# datalogger-v10.net
KiCad netlist of a schematic drawn in EAGLE
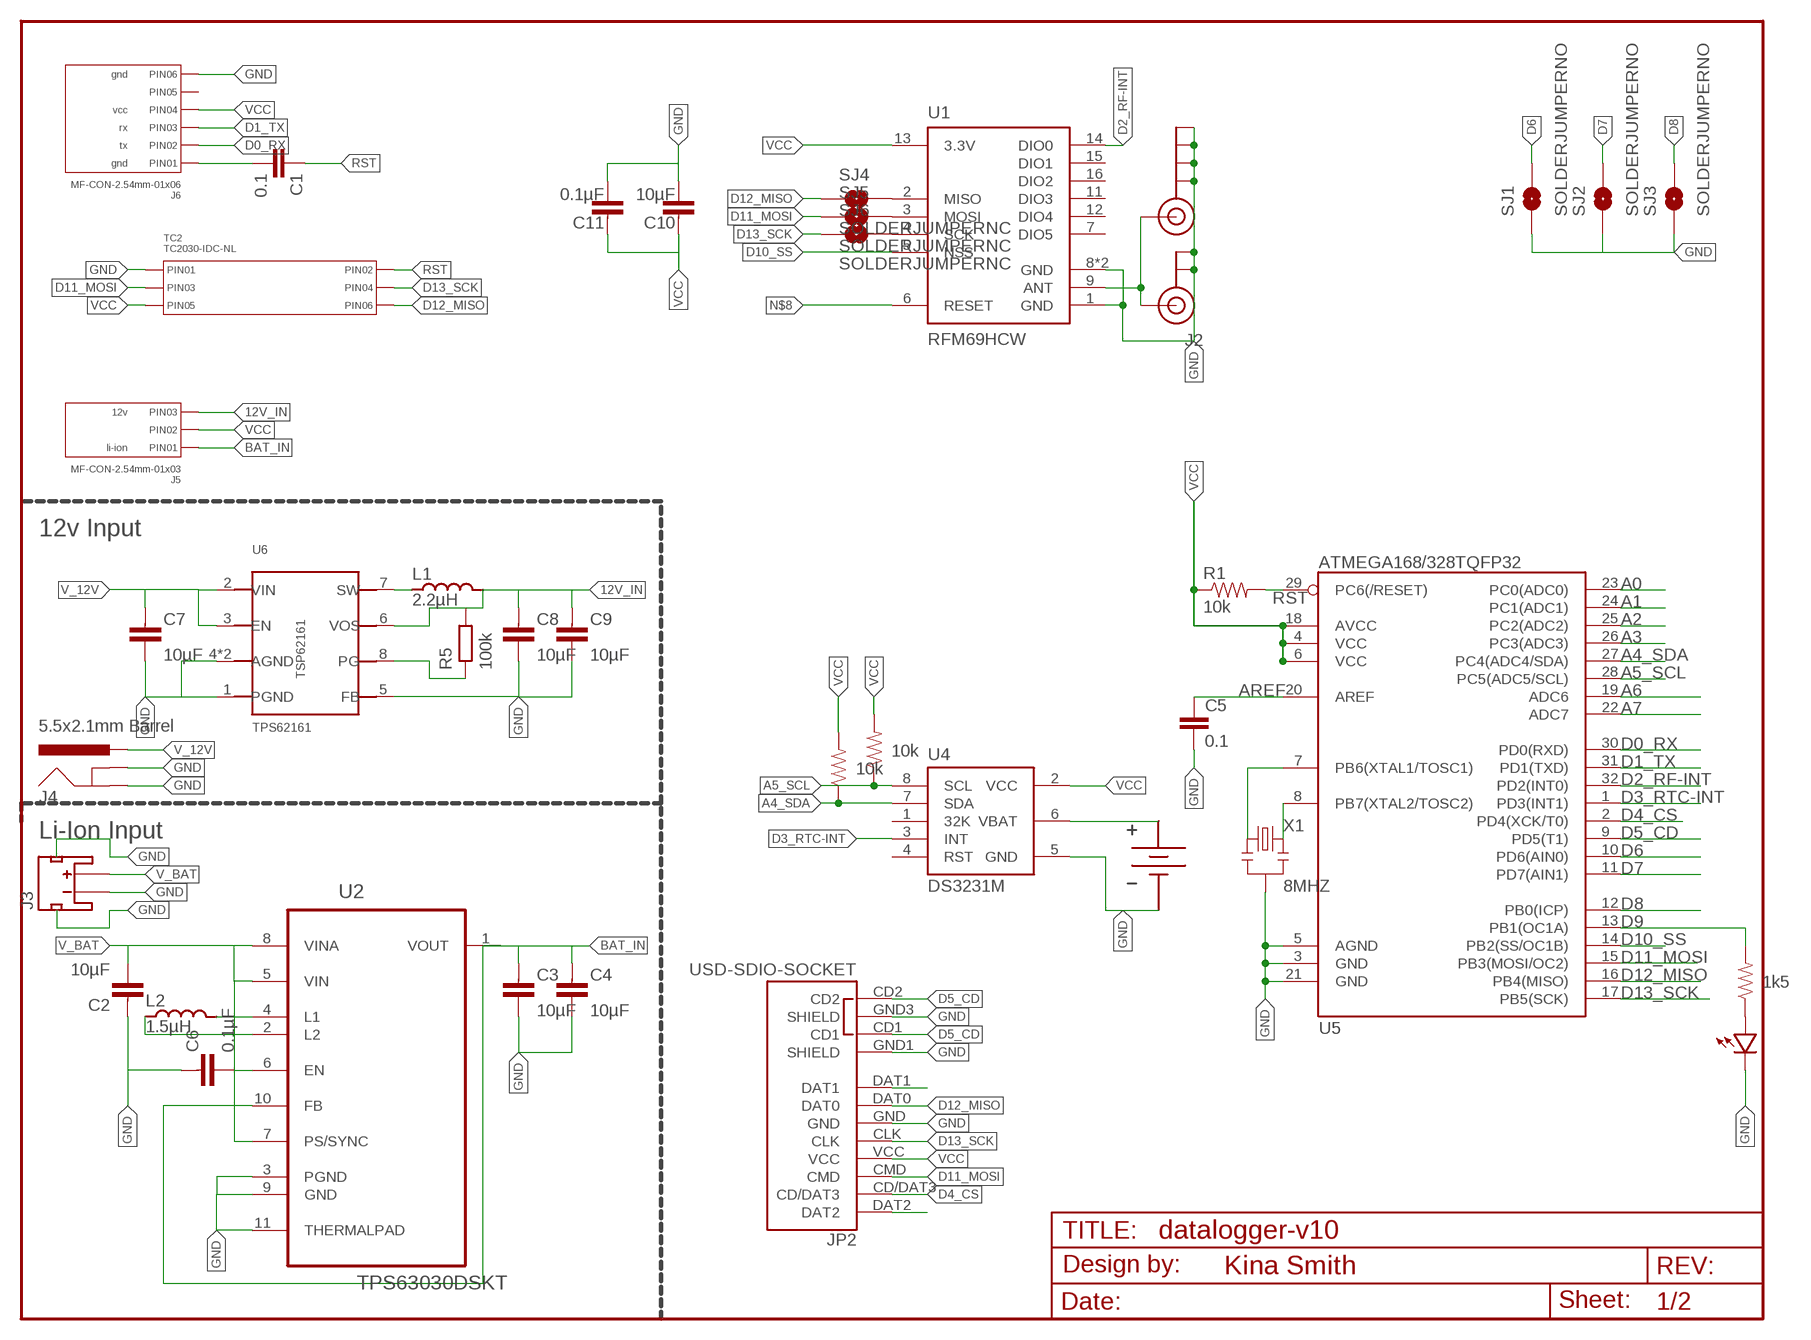
[diagram p0: schematic, sheet 1]
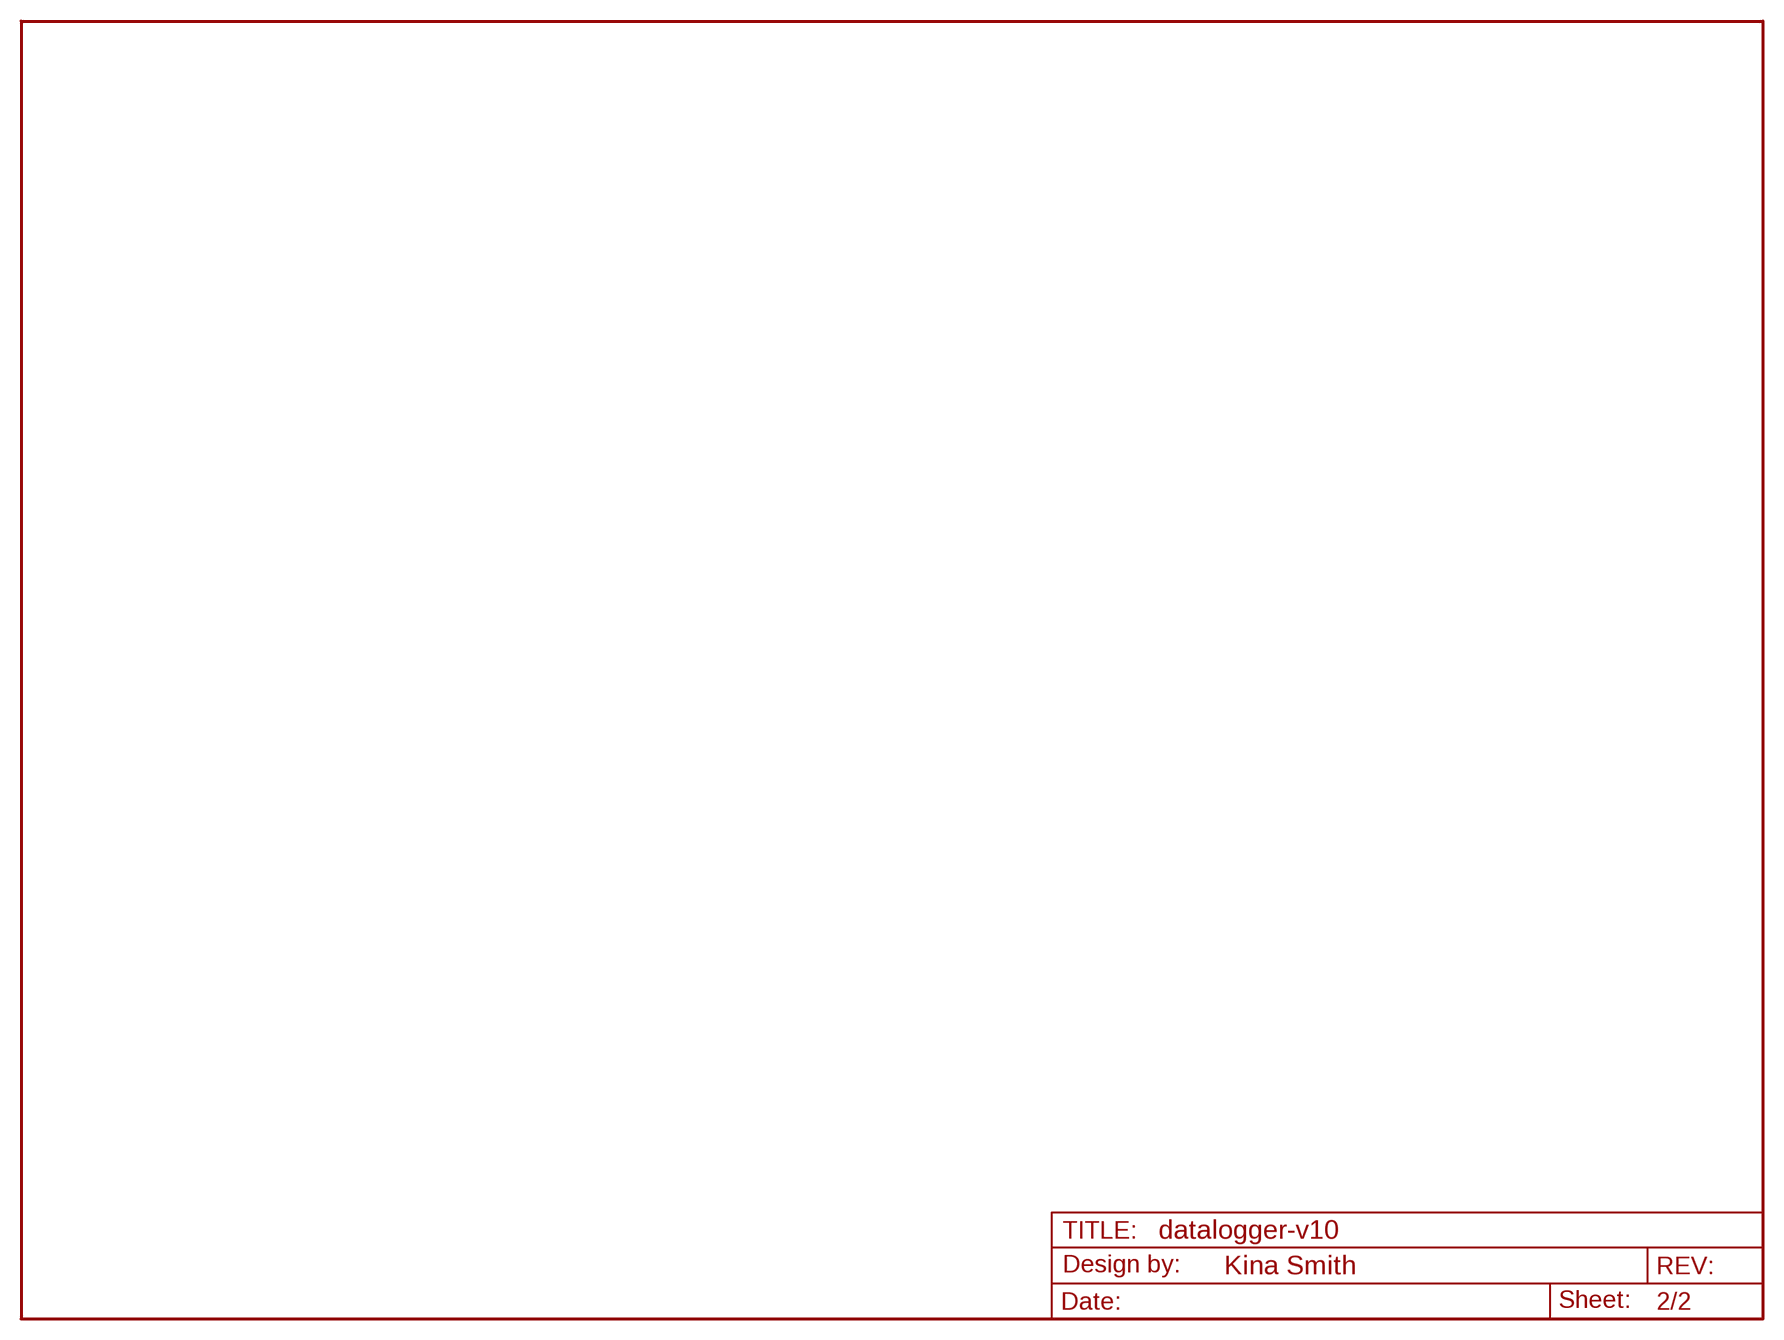
[diagram p1: schematic, sheet 2]

(export (version "E")
  (design (tool "Eeschema 10.0.6"))
  (components
    (comp (ref "C1")
      (value "0.1")
      (footprint "eagle-import:0603-CAP")
      (libsource (lib "eagle-import") (part "CAP0603-CAP"))
    )
    (comp (ref "C2")
      (value "10µF")
      (footprint "eagle-import:C0805-N")
      (libsource (lib "eagle-import") (part "passives-7351_CAPACITOR0805-N"))
    )
    (comp (ref "C3")
      (value "10µF")
      (footprint "eagle-import:C0805-N")
      (libsource (lib "eagle-import") (part "passives-7351_CAPACITOR0805-N"))
    )
    (comp (ref "C4")
      (value "10µF")
      (footprint "eagle-import:C0805-N")
      (libsource (lib "eagle-import") (part "passives-7351_CAPACITOR0805-N"))
    )
    (comp (ref "C5")
      (value "0.1")
      (footprint "eagle-import:0603-CAP")
      (libsource (lib "eagle-import") (part "CAP0603-CAP"))
    )
    (comp (ref "C6")
      (value "0.1µF")
      (footprint "eagle-import:C0603-N")
      (libsource (lib "eagle-import") (part "passives-7351_CAPACITOR0603-N"))
    )
    (comp (ref "C7")
      (value "10µF")
      (footprint "eagle-import:C0805-N")
      (libsource (lib "eagle-import") (part "passives-7351_CAPACITOR0805-N"))
    )
    (comp (ref "C8")
      (value "10µF")
      (footprint "eagle-import:C0805-N")
      (libsource (lib "eagle-import") (part "passives-7351_CAPACITOR0805-N"))
    )
    (comp (ref "C9")
      (value "10µF")
      (footprint "eagle-import:C0805-N")
      (libsource (lib "eagle-import") (part "passives-7351_CAPACITOR0805-N"))
    )
    (comp (ref "C10")
      (value "10µF")
      (footprint "eagle-import:C0805-N")
      (libsource (lib "eagle-import") (part "CAPACITOR0805-N"))
    )
    (comp (ref "C11")
      (value "0.1µF")
      (footprint "eagle-import:C0603-N")
      (libsource (lib "eagle-import") (part "CAPACITOR0603-N"))
    )
    (comp (ref "FRAME1")
      (value "FRAME-LETTERNO_PACKAGE")
      (footprint "eagle-import:DUMMY")
      (fields (field (name "DESIGNER") "Nobody"))
      (libsource (lib "eagle-import") (part "FRAME-LETTERNO_PACKAGE"))
    )
    (comp (ref "J$1")
      (value "SMA_EDGE")
      (footprint "eagle-import:SMA-EDGE")
      (libsource (lib "eagle-import") (part "SMA_EDGE"))
    )
    (comp (ref "J2")
      (value "U.FL")
      (footprint "eagle-import:U.FL")
      (libsource (lib "eagle-import") (part "U.FL"))
    )
    (comp (ref "J3")
      (value "JST_2MM_MALE")
      (footprint "eagle-import:JST-2-SMD")
      (libsource (lib "eagle-import") (part "JST_2MM_MALE"))
    )
    (comp (ref "J4")
      (value "5.5x2.1mm Barrel")
      (footprint "eagle-import:POWER_JACK_SMD")
      (libsource (lib "eagle-import") (part "POWER_JACKSMD"))
    )
    (comp (ref "J5")
      (value "MF-CON-2.54mm-01x03")
      (footprint "eagle-import:PTH_2.54MM_01X03")
      (fields
        (field (name "HOUSEPART") "YES")
        (field (name "LABEL01") "li-ion")
        (field (name "LABEL03") "12v")
      )
      (libsource (lib "eagle-import") (part "CON_01X03_PTH_2.54MM"))
    )
    (comp (ref "J6")
      (value "MF-CON-2.54mm-01x06")
      (footprint "eagle-import:PTH_2.54MM_01X06")
      (fields
        (field (name "HOUSEPART") "YES")
        (field (name "LABEL01") "gnd")
        (field (name "LABEL02") "tx")
        (field (name "LABEL03") "rx")
        (field (name "LABEL04") "vcc")
        (field (name "LABEL06") "gnd")
      )
      (libsource (lib "eagle-import") (part "CON_01X06_PTH_2.54MM"))
    )
    (comp (ref "JP2")
      (value "USD-SDIO-SOCKET")
      (footprint "eagle-import:MICRO-SD-SOCKET-SDIO")
      (libsource (lib "eagle-import") (part "USD-SDIO-SOCKET"))
    )
    (comp (ref "L1")
      (value "2.2µH")
      (footprint "eagle-import:IND_2.5X2")
      (libsource (lib "eagle-import") (part "INDUCTOR2520"))
    )
    (comp (ref "L2")
      (value "1.5µH")
      (footprint "eagle-import:IND_3X3")
      (libsource (lib "eagle-import") (part "INDUCTOR3030"))
    )
    (comp (ref "R1")
      (value "10k")
      (footprint "eagle-import:0603-RES")
      (libsource (lib "eagle-import") (part "RESISTOR0603-RES"))
    )
    (comp (ref "R2")
      (value "1k5")
      (footprint "eagle-import:0603-RES")
      (libsource (lib "eagle-import") (part "RESISTOR0603-RES"))
    )
    (comp (ref "R3")
      (value "10k")
      (footprint "eagle-import:0603-RES")
      (libsource (lib "eagle-import") (part "RESISTOR0603-RES"))
    )
    (comp (ref "R4")
      (value "10k")
      (footprint "eagle-import:0603-RES")
      (libsource (lib "eagle-import") (part "RESISTOR0603-RES"))
    )
    (comp (ref "R5")
      (value "100k")
      (footprint "eagle-import:R0603-N")
      (libsource (lib "eagle-import") (part "RESISTOR0603-N"))
    )
    (comp (ref "SJ1")
      (value "SOLDERJUMPERNO")
      (footprint "eagle-import:SJ_2S-NO")
      (libsource (lib "eagle-import") (part "SOLDERJUMPERNO"))
    )
    (comp (ref "SJ2")
      (value "SOLDERJUMPERNO")
      (footprint "eagle-import:SJ_2S-NO")
      (libsource (lib "eagle-import") (part "SOLDERJUMPERNO"))
    )
    (comp (ref "SJ3")
      (value "SOLDERJUMPERNO")
      (footprint "eagle-import:SJ_2S-NO")
      (libsource (lib "eagle-import") (part "SOLDERJUMPERNO"))
    )
    (comp (ref "SJ4")
      (value "SOLDERJUMPERNC")
      (footprint "eagle-import:SJ_2S")
      (libsource (lib "eagle-import") (part "SOLDERJUMPERNC"))
    )
    (comp (ref "SJ5")
      (value "SOLDERJUMPERNC")
      (footprint "eagle-import:SJ_2S")
      (libsource (lib "eagle-import") (part "SOLDERJUMPERNC"))
    )
    (comp (ref "SJ6")
      (value "SOLDERJUMPERNC")
      (footprint "eagle-import:SJ_2S")
      (libsource (lib "eagle-import") (part "SOLDERJUMPERNC"))
    )
    (comp (ref "TC2")
      (value "TC2030-IDC-NL")
      (footprint "eagle-import:TC2030-IDC-NL")
      (fields (field (name "HOUSEPART") "NO"))
      (libsource (lib "eagle-import") (part "CON_02X03_TC2030-IDC-NL_AVRISP"))
    )
    (comp (ref "U$1")
      (value "BATTERY_HOLDER12MM")
      (footprint "eagle-import:BATTCON_12MM")
      (libsource (lib "eagle-import") (part "BATTERY_HOLDER12MM"))
    )
    (comp (ref "U$2")
      (value "LED0603")
      (footprint "eagle-import:0603-LED")
      (libsource (lib "eagle-import") (part "LED0603"))
    )
    (comp (ref "U1")
      (value "RFM69HCW")
      (footprint "eagle-import:RFM69HCW-XXXS2")
      (libsource (lib "eagle-import") (part "RFM69HCW"))
    )
    (comp (ref "U2")
      (value "TPS63030DSKT")
      (footprint "eagle-import:SON50P260X260X80-11N")
      (libsource (lib "eagle-import") (part "TPS63030DSKT"))
    )
    (comp (ref "U4")
      (value "DS3231M")
      (footprint "eagle-import:SO08")
      (libsource (lib "eagle-import") (part "DS3231M"))
    )
    (comp (ref "U5")
      (value "ATMEGA168/328TQFP32")
      (footprint "eagle-import:TQFP32-08")
      (libsource (lib "eagle-import") (part "ATMEGA168/328TQFP32"))
    )
    (comp (ref "U6")
      (value "TPS62161")
      (footprint "eagle-import:WSON-8")
      (fields (field (name "PARTNO") "TPS62161DSGR"))
      (libsource (lib "eagle-import") (part "TPS62161"))
    )
    (comp (ref "X1")
      (value "8MHZ")
      (footprint "eagle-import:RESONATOR-SMD")
      (libsource (lib "eagle-import") (part "RESONATORSMD"))
    )
    (comp (ref "FRAME3")
      (value "FRAME-LETTERNO_PACKAGE")
      (footprint "eagle-import:DUMMY")
      (fields (field (name "DESIGNER") "Nobody"))
      (libsource (lib "eagle-import") (part "FRAME-LETTERNO_PACKAGE"))
    )
  )
  (nets
    (net (code "1") (name "12V_IN") (class "Default")
      (node (ref "C8") (pin "1") (pinfunction "1_1") (pintype "passive"))
      (node (ref "C9") (pin "1") (pinfunction "1_1") (pintype "passive"))
      (node (ref "J5") (pin "P$3") (pinfunction "PIN3_P$3") (pintype "bidirectional"))
      (node (ref "L1") (pin "P$2") (pinfunction "P$2_P$2") (pintype "passive"))
      (node (ref "R5") (pin "2") (pinfunction "P$2_2") (pintype "passive"))
      (node (ref "U6") (pin "6") (pinfunction "VOS_6") (pintype "bidirectional"))
    )
    (net (code "2") (name "A0") (class "Default")
      (node (ref "U5") (pin "23") (pinfunction "PC0(ADC0)_23") (pintype "bidirectional"))
    )
    (net (code "3") (name "A1") (class "Default")
      (node (ref "U5") (pin "24") (pinfunction "PC1(ADC1)_24") (pintype "bidirectional"))
    )
    (net (code "4") (name "A2") (class "Default")
      (node (ref "U5") (pin "25") (pinfunction "PC2(ADC2)_25") (pintype "bidirectional"))
    )
    (net (code "5") (name "A3") (class "Default")
      (node (ref "U5") (pin "26") (pinfunction "PC3(ADC3)_26") (pintype "bidirectional"))
    )
    (net (code "6") (name "A4_SDA") (class "Default")
      (node (ref "R4") (pin "1") (pinfunction "1_1") (pintype "passive"))
      (node (ref "U4") (pin "7") (pinfunction "SDA_7") (pintype "bidirectional"))
      (node (ref "U5") (pin "27") (pinfunction "PC4(ADC4/SDA)_27") (pintype "bidirectional"))
    )
    (net (code "7") (name "A5_SCL") (class "Default")
      (node (ref "R3") (pin "1") (pinfunction "1_1") (pintype "passive"))
      (node (ref "U4") (pin "8") (pinfunction "SCL_8") (pintype "bidirectional"))
      (node (ref "U5") (pin "28") (pinfunction "PC5(ADC5/SCL)_28") (pintype "bidirectional"))
    )
    (net (code "8") (name "A6") (class "Default")
      (node (ref "U5") (pin "19") (pinfunction "ADC6_19") (pintype "bidirectional"))
    )
    (net (code "9") (name "A7") (class "Default")
      (node (ref "U5") (pin "22") (pinfunction "ADC7_22") (pintype "bidirectional"))
    )
    (net (code "10") (name "AREF") (class "Default")
      (node (ref "C5") (pin "1") (pinfunction "1_1") (pintype "passive"))
      (node (ref "U5") (pin "20") (pinfunction "AREF_20") (pintype "bidirectional"))
    )
    (net (code "11") (name "BAT_IN") (class "Default")
      (node (ref "C3") (pin "1") (pinfunction "1_1") (pintype "passive"))
      (node (ref "C4") (pin "1") (pinfunction "1_1") (pintype "passive"))
      (node (ref "J5") (pin "P$1") (pinfunction "PIN1_P$1") (pintype "bidirectional"))
      (node (ref "U2") (pin "1") (pinfunction "VOUT_1") (pintype "output"))
      (node (ref "U2") (pin "10") (pinfunction "FB_10") (pintype "input"))
    )
    (net (code "12") (name "D0_RX") (class "Default")
      (node (ref "J6") (pin "P$2") (pinfunction "PIN2_P$2") (pintype "bidirectional"))
      (node (ref "U5") (pin "30") (pinfunction "PD0(RXD)_30") (pintype "bidirectional"))
    )
    (net (code "13") (name "D1_TX") (class "Default")
      (node (ref "J6") (pin "P$3") (pinfunction "PIN3_P$3") (pintype "bidirectional"))
      (node (ref "U5") (pin "31") (pinfunction "PD1(TXD)_31") (pintype "bidirectional"))
    )
    (net (code "14") (name "D2_RF-INT") (class "Default")
      (node (ref "U1") (pin "14") (pinfunction "DIO0_14") (pintype "bidirectional"))
      (node (ref "U5") (pin "32") (pinfunction "PD2(INT0)_32") (pintype "bidirectional"))
    )
    (net (code "15") (name "D3_RTC-INT") (class "Default")
      (node (ref "U4") (pin "3") (pinfunction "INT_3") (pintype "bidirectional"))
      (node (ref "U5") (pin "1") (pinfunction "PD3(INT1)_1") (pintype "bidirectional"))
    )
    (net (code "16") (name "D4_CS") (class "Default")
      (node (ref "JP2") (pin "CD/DAT3") (pinfunction "CD/DAT3_CD/DAT3") (pintype "bidirectional"))
      (node (ref "U5") (pin "2") (pinfunction "PD4(XCK/T0)_2") (pintype "bidirectional"))
    )
    (net (code "17") (name "D5_CD") (class "Default")
      (node (ref "JP2") (pin "CD1") (pinfunction "CD1_CD1") (pintype "bidirectional"))
      (node (ref "JP2") (pin "CD2") (pinfunction "CD2_CD2") (pintype "bidirectional"))
      (node (ref "U5") (pin "9") (pinfunction "PD5(T1)_9") (pintype "bidirectional"))
    )
    (net (code "18") (name "D6") (class "Default")
      (node (ref "SJ1") (pin "2") (pinfunction "2_2") (pintype "passive"))
      (node (ref "U5") (pin "10") (pinfunction "PD6(AIN0)_10") (pintype "bidirectional"))
    )
    (net (code "19") (name "D7") (class "Default")
      (node (ref "SJ2") (pin "2") (pinfunction "2_2") (pintype "passive"))
      (node (ref "U5") (pin "11") (pinfunction "PD7(AIN1)_11") (pintype "bidirectional"))
    )
    (net (code "20") (name "D8") (class "Default")
      (node (ref "SJ3") (pin "2") (pinfunction "2_2") (pintype "passive"))
      (node (ref "U5") (pin "12") (pinfunction "PB0(ICP)_12") (pintype "bidirectional"))
    )
    (net (code "21") (name "D9") (class "Default")
      (node (ref "R2") (pin "2") (pinfunction "2_2") (pintype "passive"))
      (node (ref "U5") (pin "13") (pinfunction "PB1(OC1A)_13") (pintype "bidirectional"))
    )
    (net (code "22") (name "D10_SS") (class "Default")
      (node (ref "U1") (pin "5") (pinfunction "NSS_5") (pintype "input"))
      (node (ref "U5") (pin "14") (pinfunction "PB2(SS/OC1B)_14") (pintype "bidirectional"))
    )
    (net (code "23") (name "D11_MOSI") (class "Default")
      (node (ref "JP2") (pin "CMD") (pinfunction "CMD_CMD") (pintype "bidirectional"))
      (node (ref "SJ5") (pin "1") (pinfunction "1_1") (pintype "passive"))
      (node (ref "TC2") (pin "P$3") (pinfunction "PIN3_P$3") (pintype "bidirectional"))
      (node (ref "U5") (pin "15") (pinfunction "PB3(MOSI/OC2)_15") (pintype "bidirectional"))
    )
    (net (code "24") (name "D12_MISO") (class "Default")
      (node (ref "JP2") (pin "DAT0") (pinfunction "DAT0_DAT0") (pintype "bidirectional"))
      (node (ref "SJ4") (pin "1") (pinfunction "1_1") (pintype "passive"))
      (node (ref "TC2") (pin "P$6") (pinfunction "PIN6_P$6") (pintype "bidirectional"))
      (node (ref "U5") (pin "16") (pinfunction "PB4(MISO)_16") (pintype "bidirectional"))
    )
    (net (code "25") (name "D13_SCK") (class "Default")
      (node (ref "JP2") (pin "CLK") (pinfunction "CLK_CLK") (pintype "bidirectional"))
      (node (ref "SJ6") (pin "1") (pinfunction "1_1") (pintype "passive"))
      (node (ref "TC2") (pin "P$4") (pinfunction "PIN4_P$4") (pintype "bidirectional"))
      (node (ref "U5") (pin "17") (pinfunction "PB5(SCK)_17") (pintype "bidirectional"))
    )
    (net (code "26") (name "GND") (class "Default")
      (node (ref "C10") (pin "2") (pinfunction "2_2") (pintype "passive"))
      (node (ref "C11") (pin "2") (pinfunction "2_2") (pintype "passive"))
      (node (ref "C2") (pin "1") (pinfunction "1_1") (pintype "passive"))
      (node (ref "C3") (pin "2") (pinfunction "2_2") (pintype "passive"))
      (node (ref "C4") (pin "2") (pinfunction "2_2") (pintype "passive"))
      (node (ref "C5") (pin "2") (pinfunction "2_2") (pintype "passive"))
      (node (ref "C6") (pin "1") (pinfunction "1_1") (pintype "passive"))
      (node (ref "C7") (pin "2") (pinfunction "2_2") (pintype "passive"))
      (node (ref "C8") (pin "2") (pinfunction "2_2") (pintype "passive"))
      (node (ref "C9") (pin "2") (pinfunction "2_2") (pintype "passive"))
      (node (ref "J$1") (pin "GND@0") (pinfunction "GND_GND@0") (pintype "bidirectional"))
      (node (ref "J$1") (pin "GND@1") (pinfunction "GND_GND@1") (pintype "bidirectional"))
      (node (ref "J$1") (pin "GND@2") (pinfunction "GND_GND@2") (pintype "bidirectional"))
      (node (ref "J$1") (pin "GND@3") (pinfunction "GND_GND@3") (pintype "bidirectional"))
      (node (ref "J2") (pin "P$1") (pinfunction "GND_P$1") (pintype "bidirectional"))
      (node (ref "J2") (pin "P$2") (pinfunction "GND_P$2") (pintype "bidirectional"))
      (node (ref "J3") (pin "1") (pinfunction "-_1") (pintype "bidirectional"))
      (node (ref "J3") (pin "NC1") (pinfunction "PAD1_NC1") (pintype "bidirectional"))
      (node (ref "J3") (pin "NC2") (pinfunction "PAD2_NC2") (pintype "bidirectional"))
      (node (ref "J4") (pin "GND") (pinfunction "GNDBREAK_GND") (pintype "bidirectional"))
      (node (ref "J4") (pin "P$4") (pinfunction "GND_P$4") (pintype "bidirectional"))
      (node (ref "J6") (pin "P$6") (pinfunction "PIN6_P$6") (pintype "bidirectional"))
      (node (ref "JP2") (pin "GND") (pinfunction "GND_GND") (pintype "bidirectional"))
      (node (ref "JP2") (pin "GND1") (pinfunction "SHIELD_GND1") (pintype "bidirectional"))
      (node (ref "JP2") (pin "GND3") (pinfunction "SHIELD_GND3") (pintype "bidirectional"))
      (node (ref "SJ1") (pin "1") (pinfunction "1_1") (pintype "passive"))
      (node (ref "SJ2") (pin "1") (pinfunction "1_1") (pintype "passive"))
      (node (ref "SJ3") (pin "1") (pinfunction "1_1") (pintype "passive"))
      (node (ref "TC2") (pin "P$1") (pinfunction "PIN1_P$1") (pintype "bidirectional"))
      (node (ref "U$1") (pin "GND") (pinfunction "GND_GND") (pintype "bidirectional"))
      (node (ref "U$2") (pin "MINUS") (pinfunction "MINUS_MINUS") (pintype "passive"))
      (node (ref "U1") (pin "1") (pinfunction "GND_1") (pintype "power_in"))
      (node (ref "U1") (pin "10") (pinfunction "GND_10") (pintype "power_in"))
      (node (ref "U1") (pin "8") (pinfunction "GND_8") (pintype "power_in"))
      (node (ref "U2") (pin "11") (pinfunction "THERMALPAD_11") (pintype "passive"))
      (node (ref "U2") (pin "3") (pinfunction "PGND_3") (pintype "passive"))
      (node (ref "U2") (pin "9") (pinfunction "GND_9") (pintype "passive"))
      (node (ref "U4") (pin "5") (pinfunction "GND_5") (pintype "power_in"))
      (node (ref "U5") (pin "21") (pinfunction "GND_21") (pintype "bidirectional"))
      (node (ref "U5") (pin "3") (pinfunction "GND_3") (pintype "bidirectional"))
      (node (ref "U5") (pin "5") (pinfunction "AGND_5") (pintype "bidirectional"))
      (node (ref "U6") (pin "1") (pinfunction "PGND_1") (pintype "bidirectional"))
      (node (ref "U6") (pin "4") (pinfunction "AGND_4") (pintype "bidirectional"))
      (node (ref "U6") (pin "5") (pinfunction "FB_5") (pintype "bidirectional"))
      (node (ref "U6") (pin "P$9") (pinfunction "AGND_P$9") (pintype "bidirectional"))
      (node (ref "X1") (pin "2") (pinfunction "2_2") (pintype "passive"))
    )
    (net (code "27") (name "N$8") (class "Default")
      (node (ref "U1") (pin "6") (pinfunction "RESET_6") (pintype "input"))
    )
    (net (code "28") (name "Net-(J$1-SIGNAL)") (class "Default")
      (node (ref "J$1") (pin "SIG") (pinfunction "SIGNAL_SIG") (pintype "bidirectional"))
      (node (ref "J2") (pin "P$3") (pinfunction "SIGNAL_P$3") (pintype "bidirectional"))
      (node (ref "U1") (pin "9") (pinfunction "ANT_9") (pintype "passive"))
    )
    (net (code "29") (name "Net-(J6-PIN1)") (class "Default")
      (node (ref "C1") (pin "2") (pinfunction "2_2") (pintype "passive"))
      (node (ref "J6") (pin "P$1") (pinfunction "PIN1_P$1") (pintype "bidirectional"))
    )
    (net (code "30") (name "Net-(R2-Pad1)") (class "Default")
      (node (ref "R2") (pin "1") (pinfunction "1_1") (pintype "passive"))
      (node (ref "U$2") (pin "PLUS") (pinfunction "PLUS_PLUS") (pintype "passive"))
    )
    (net (code "31") (name "Net-(R5-P$1)") (class "Default")
      (node (ref "R5") (pin "1") (pinfunction "P$1_1") (pintype "passive"))
      (node (ref "U6") (pin "8") (pinfunction "PG_8") (pintype "bidirectional"))
    )
    (net (code "32") (name "Net-(U1-MISO)") (class "Default")
      (node (ref "SJ4") (pin "2") (pinfunction "2_2") (pintype "passive"))
      (node (ref "U1") (pin "2") (pinfunction "MISO_2") (pintype "bidirectional"))
    )
    (net (code "33") (name "Net-(U1-MOSI)") (class "Default")
      (node (ref "SJ5") (pin "2") (pinfunction "2_2") (pintype "passive"))
      (node (ref "U1") (pin "3") (pinfunction "MOSI_3") (pintype "input"))
    )
    (net (code "34") (name "Net-(U1-SCK)") (class "Default")
      (node (ref "SJ6") (pin "2") (pinfunction "2_2") (pintype "passive"))
      (node (ref "U1") (pin "4") (pinfunction "SCK_4") (pintype "input"))
    )
    (net (code "35") (name "Net-(U2-L1)") (class "Default")
      (node (ref "L2") (pin "P$2") (pinfunction "P$2_P$2") (pintype "passive"))
      (node (ref "U2") (pin "4") (pinfunction "L1_4") (pintype "input"))
    )
    (net (code "36") (name "Net-(U2-L2)") (class "Default")
      (node (ref "L2") (pin "P$1") (pinfunction "P$1_P$1") (pintype "passive"))
      (node (ref "U2") (pin "2") (pinfunction "L2_2") (pintype "input"))
    )
    (net (code "37") (name "Net-(U4-VBAT)") (class "Default")
      (node (ref "U$1") (pin "PWR@1") (pinfunction "VBAT_PWR@1") (pintype "bidirectional"))
      (node (ref "U$1") (pin "PWR@2") (pinfunction "VBAT_PWR@2") (pintype "bidirectional"))
      (node (ref "U4") (pin "6") (pinfunction "VBAT_6") (pintype "power_in"))
    )
    (net (code "38") (name "Net-(U5-PB6(XTAL1{slash}TOSC1))") (class "Default")
      (node (ref "U5") (pin "7") (pinfunction "PB6(XTAL1/TOSC1)_7") (pintype "bidirectional"))
      (node (ref "X1") (pin "1") (pinfunction "1_1") (pintype "passive"))
    )
    (net (code "39") (name "Net-(U5-PB7(XTAL2{slash}TOSC2))") (class "Default")
      (node (ref "U5") (pin "8") (pinfunction "PB7(XTAL2/TOSC2)_8") (pintype "bidirectional"))
      (node (ref "X1") (pin "3") (pinfunction "3_3") (pintype "passive"))
    )
    (net (code "40") (name "Net-(U6-SW)") (class "Default")
      (node (ref "L1") (pin "P$1") (pinfunction "P$1_P$1") (pintype "passive"))
      (node (ref "U6") (pin "7") (pinfunction "SW_7") (pintype "bidirectional"))
    )
    (net (code "41") (name "RST") (class "Default")
      (node (ref "C1") (pin "1") (pinfunction "1_1") (pintype "passive"))
      (node (ref "R1") (pin "2") (pinfunction "2_2") (pintype "passive"))
      (node (ref "TC2") (pin "P$2") (pinfunction "PIN2_P$2") (pintype "bidirectional"))
      (node (ref "U5") (pin "29") (pinfunction "PC6(/RESET)_29") (pintype "bidirectional"))
    )
    (net (code "42") (name "VCC") (class "Default")
      (node (ref "C10") (pin "1") (pinfunction "1_1") (pintype "passive"))
      (node (ref "C11") (pin "1") (pinfunction "1_1") (pintype "passive"))
      (node (ref "J5") (pin "P$2") (pinfunction "PIN2_P$2") (pintype "bidirectional"))
      (node (ref "J6") (pin "P$4") (pinfunction "PIN4_P$4") (pintype "bidirectional"))
      (node (ref "JP2") (pin "VCC") (pinfunction "VCC_VCC") (pintype "bidirectional"))
      (node (ref "R1") (pin "1") (pinfunction "1_1") (pintype "passive"))
      (node (ref "R3") (pin "2") (pinfunction "2_2") (pintype "passive"))
      (node (ref "R4") (pin "2") (pinfunction "2_2") (pintype "passive"))
      (node (ref "TC2") (pin "P$5") (pinfunction "PIN5_P$5") (pintype "bidirectional"))
      (node (ref "U1") (pin "13") (pinfunction "3.3V_13") (pintype "power_in"))
      (node (ref "U4") (pin "2") (pinfunction "VCC_2") (pintype "power_in"))
      (node (ref "U5") (pin "18") (pinfunction "AVCC_18") (pintype "bidirectional"))
      (node (ref "U5") (pin "4") (pinfunction "VCC_4") (pintype "bidirectional"))
      (node (ref "U5") (pin "6") (pinfunction "VCC_6") (pintype "bidirectional"))
    )
    (net (code "43") (name "V_12V") (class "Default")
      (node (ref "C7") (pin "1") (pinfunction "1_1") (pintype "passive"))
      (node (ref "J4") (pin "VIN0") (pinfunction "PWR_VIN0") (pintype "bidirectional"))
      (node (ref "U6") (pin "2") (pinfunction "VIN_2") (pintype "bidirectional"))
      (node (ref "U6") (pin "3") (pinfunction "EN_3") (pintype "bidirectional"))
    )
    (net (code "44") (name "V_BAT") (class "Default")
      (node (ref "C2") (pin "2") (pinfunction "2_2") (pintype "passive"))
      (node (ref "C6") (pin "2") (pinfunction "2_2") (pintype "passive"))
      (node (ref "J3") (pin "2") (pinfunction "+_2") (pintype "bidirectional"))
      (node (ref "U2") (pin "5") (pinfunction "VIN_5") (pintype "input"))
      (node (ref "U2") (pin "6") (pinfunction "EN_6") (pintype "input"))
      (node (ref "U2") (pin "7") (pinfunction "PS/SYNC_7") (pintype "input"))
      (node (ref "U2") (pin "8") (pinfunction "VINA_8") (pintype "input"))
    )
    (net (code "45") (name "unconnected-(J6-PIN5-PadP$5)") (class "Default")
      (node (ref "J6") (pin "P$5") (pinfunction "PIN5_P$5") (pintype "bidirectional"))
    )
    (net (code "46") (name "unconnected-(JP2-PadDAT1)") (class "Default")
      (node (ref "JP2") (pin "DAT1") (pinfunction "DAT1_DAT1") (pintype "bidirectional"))
    )
    (net (code "47") (name "unconnected-(JP2-PadDAT2)") (class "Default")
      (node (ref "JP2") (pin "DAT2") (pinfunction "DAT2_DAT2") (pintype "bidirectional"))
    )
    (net (code "48") (name "unconnected-(U1-DIO1-Pad15)") (class "Default")
      (node (ref "U1") (pin "15") (pinfunction "DIO1_15") (pintype "bidirectional"))
    )
    (net (code "49") (name "unconnected-(U1-DIO2-Pad16)") (class "Default")
      (node (ref "U1") (pin "16") (pinfunction "DIO2_16") (pintype "bidirectional"))
    )
    (net (code "50") (name "unconnected-(U1-DIO3-Pad11)") (class "Default")
      (node (ref "U1") (pin "11") (pinfunction "DIO3_11") (pintype "bidirectional"))
    )
    (net (code "51") (name "unconnected-(U1-DIO4-Pad12)") (class "Default")
      (node (ref "U1") (pin "12") (pinfunction "DIO4_12") (pintype "bidirectional"))
    )
    (net (code "52") (name "unconnected-(U1-DIO5-Pad7)") (class "Default")
      (node (ref "U1") (pin "7") (pinfunction "DIO5_7") (pintype "bidirectional"))
    )
    (net (code "53") (name "unconnected-(U4-32K-Pad1)") (class "Default")
      (node (ref "U4") (pin "1") (pinfunction "32K_1") (pintype "bidirectional"))
    )
    (net (code "54") (name "unconnected-(U4-RST-Pad4)") (class "Default")
      (node (ref "U4") (pin "4") (pinfunction "RST_4") (pintype "bidirectional"))
    )
  )
)
